# Sheet1.net
KiCad netlist of a schematic drawn in Altium Designer
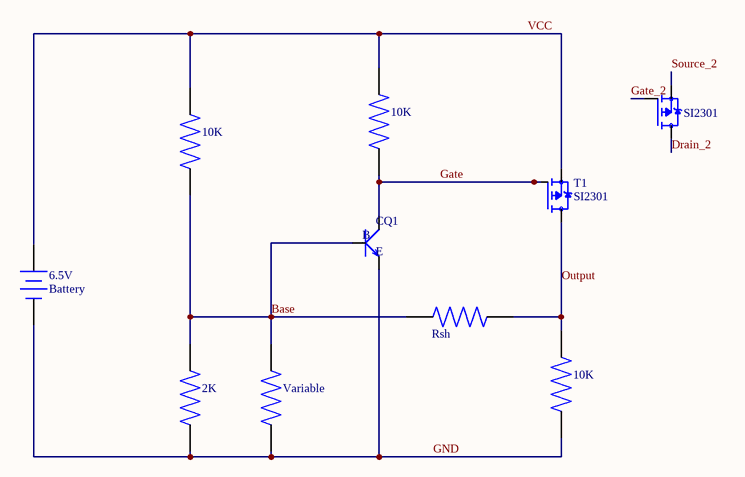
[diagram p0: Sheet1.SchDoc]

(export (version "E")
  (design (tool "Eeschema 10.0.6"))
  (components
    (comp (ref "6.5V")
      (value "Battery")
      (footprint "BAT-2")
      (description "Multicell Battery")
      (fields (field (name "PUBLISHER") "Altium Limited"))
      (libsource (lib "Miscellaneous Devices") (part "Battery"))
    )
    (comp (ref "Q1")
      (value "SMD-TRANSISTORS-NPN-25V-500MW(SOT-23)")
      (footprint "SOT-23")
      (description "Bipolar (BJT) Transistor NPN 25 V 500 mA 150MHz 300 mW Surface Mount SOT-23")
      (fields (field (name "MF") "UMW") (field (name "MP") "S8050"))
      (libsource (lib "Transistor_SMD_J3Y") (part "SMD-TRANSISTORS-NPN-25V-500MW(SOT-23)"))
    )
    (comp (ref "R1")
      (value "10K")
      (footprint "RESC3216X75N")
      (description "CR1206 SMD Thick Film Resistor,jumper 0R ¦ Bourns CR1206-J/-000ELF")
      (fields (field (name "MF") "Bourns") (field (name "MP") "CR1206-J/-000ELF"))
      (libsource (lib "Resistor_SMD_1206") (part "CR1206-J/-000ELF"))
    )
    (comp (ref "R2")
      (value "2K")
      (footprint "RESC3216X75N")
      (description "CR1206 SMD Thick Film Resistor,jumper 0R ¦ Bourns CR1206-J/-000ELF")
      (fields (field (name "MF") "Bourns") (field (name "MP") "CR1206-J/-000ELF"))
      (libsource (lib "Resistor_SMD_1206") (part "CR1206-J/-000ELF"))
    )
    (comp (ref "R3")
      (value "Variable")
      (footprint "RESC3216X75N")
      (description "CR1206 SMD Thick Film Resistor,jumper 0R ¦ Bourns CR1206-J/-000ELF")
      (fields (field (name "MF") "Bourns") (field (name "MP") "CR1206-J/-000ELF"))
      (libsource (lib "Resistor_SMD_1206") (part "CR1206-J/-000ELF"))
    )
    (comp (ref "R4")
      (value "10K")
      (footprint "RESC3216X75N")
      (description "CR1206 SMD Thick Film Resistor,jumper 0R ¦ Bourns CR1206-J/-000ELF")
      (fields (field (name "MF") "Bourns") (field (name "MP") "CR1206-J/-000ELF"))
      (libsource (lib "Resistor_SMD_1206") (part "CR1206-J/-000ELF"))
    )
    (comp (ref "R5")
      (value "Rsh")
      (footprint "RESC3216X75N")
      (description "CR1206 SMD Thick Film Resistor,jumper 0R ¦ Bourns CR1206-J/-000ELF")
      (fields (field (name "MF") "Bourns") (field (name "MP") "CR1206-J/-000ELF"))
      (libsource (lib "Resistor_SMD_1206") (part "CR1206-J/-000ELF"))
    )
    (comp (ref "R6")
      (value "10K")
      (footprint "RESC3216X75N")
      (description "CR1206 SMD Thick Film Resistor,jumper 0R ¦ Bourns CR1206-J/-000ELF")
      (fields (field (name "MF") "Bourns") (field (name "MP") "CR1206-J/-000ELF"))
      (libsource (lib "Resistor_SMD_1206") (part "CR1206-J/-000ELF"))
    )
    (comp (ref "T1")
      (value "SI2301")
      (footprint "DESTO_SOT23")
      (description "MOSFET P-CH 20V 2.2A SOT23-3")
      (fields (field (name "MF") "Micro Commercial Components (MCC)"))
      (libsource (lib "MOSFET_SMD_SI2301") (part "SI2301"))
    )
    (comp (ref "T2")
      (value "SI2301")
      (footprint "DESTO_SOT23")
      (description "MOSFET P-CH 20V 2.2A SOT23-3")
      (fields (field (name "MF") "Micro Commercial Components (MCC)"))
      (libsource (lib "MOSFET_SMD_SI2301") (part "SI2301"))
    )
  )
  (nets
    (net (code "1") (name "/Base") (class "Default")
      (node (ref "Q1") (pin "1") (pinfunction "B_1") (pintype "passive"))
      (node (ref "R1") (pin "1") (pinfunction "1_1") (pintype "passive"))
      (node (ref "R2") (pin "2") (pinfunction "2_2") (pintype "passive"))
      (node (ref "R3") (pin "2") (pinfunction "2_2") (pintype "passive"))
      (node (ref "R5") (pin "1") (pinfunction "1_1") (pintype "passive"))
    )
    (net (code "2") (name "/Drain_2") (class "Default")
      (node (ref "T2") (pin "3") (pinfunction "D_3") (pintype "passive"))
    )
    (net (code "3") (name "/GND") (class "Default")
      (node (ref "6.5V") (pin "2") (pinfunction "-_2") (pintype "passive"))
      (node (ref "Q1") (pin "2") (pinfunction "E_2") (pintype "passive"))
      (node (ref "R2") (pin "1") (pinfunction "1_1") (pintype "passive"))
      (node (ref "R3") (pin "1") (pinfunction "1_1") (pintype "passive"))
      (node (ref "R6") (pin "1") (pinfunction "1_1") (pintype "passive"))
    )
    (net (code "4") (name "/Gate") (class "Default")
      (node (ref "Q1") (pin "3") (pinfunction "C_3") (pintype "passive"))
      (node (ref "R4") (pin "1") (pinfunction "1_1") (pintype "passive"))
      (node (ref "T1") (pin "1") (pinfunction "G_1") (pintype "passive"))
    )
    (net (code "5") (name "/Gate_2") (class "Default")
      (node (ref "T2") (pin "1") (pinfunction "G_1") (pintype "passive"))
    )
    (net (code "6") (name "/Output") (class "Default")
      (node (ref "R5") (pin "2") (pinfunction "2_2") (pintype "passive"))
      (node (ref "R6") (pin "2") (pinfunction "2_2") (pintype "passive"))
      (node (ref "T1") (pin "3") (pinfunction "D_3") (pintype "passive"))
    )
    (net (code "7") (name "/Source_2") (class "Default")
      (node (ref "T2") (pin "2") (pinfunction "S_2") (pintype "passive"))
    )
    (net (code "8") (name "/VCC") (class "Default")
      (node (ref "6.5V") (pin "1") (pinfunction "+_1") (pintype "passive"))
      (node (ref "R1") (pin "2") (pinfunction "2_2") (pintype "passive"))
      (node (ref "R4") (pin "2") (pinfunction "2_2") (pintype "passive"))
      (node (ref "T1") (pin "2") (pinfunction "S_2") (pintype "passive"))
    )
  )
)
